# ESP32C6.net
KiCad netlist of a schematic drawn in Altium Designer
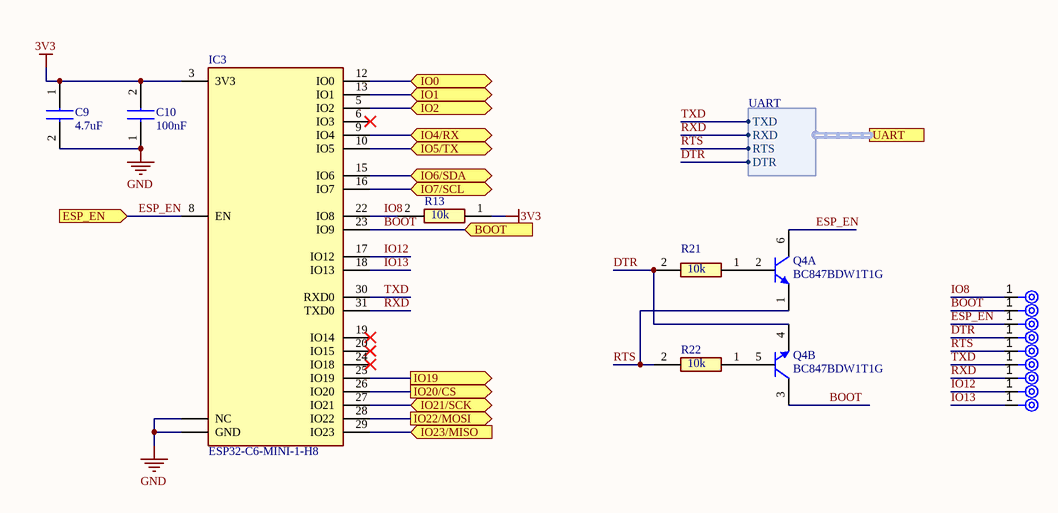
[diagram p0: ESP32C6.SchDoc]

(export (version "E")
  (design (tool "Eeschema 10.0.6"))
  (components
    (comp (ref "C9")
      (value "4.7uF")
      (footprint "SamacSys:CAPC1608X90N")
      (description "Capacitor")
      (fields
        (field (name "MANUFACTURER_PART_NUMBER") "GRM188R61E475KE11J")
        (field (name "MOUSER PART NUMBER") "81-GRM188R61E475KE1J")
      )
      (libsource (lib "*") (part "GRM188R61E475KE11J"))
    )
    (comp (ref "C10")
      (value "100nF")
      (footprint "SamacSys:CAPC1005X70N")
      (description "Capacitor")
      (fields
        (field (name "MANUFACTURER_PART_NUMBER") "GRM155R61A104KA01D")
        (field (name "MOUSER PART NUMBER") "81-GRM155R61A104KA01")
      )
      (libsource (lib "*") (part "GRM155R61A104KA01D"))
    )
    (comp (ref "IC3")
      (value "ESP32-C6-MINI-1-H8")
      (footprint "SamacSys:ESP32C6MINI1H8")
      (description "Integrated Circuit")
      (fields (field (name "MOUSER PART NUMBER") "356-ESP32C6MINI1H8"))
      (libsource (lib "SamacSys") (part "ESP32-C6-MINI-1-H8"))
    )
    (comp (ref "Q4")
      (value "BC847BDW1T1G")
      (footprint "ONSC-SOT-363-6-419B-02_W_V")
      (description "Dual General Purpose Transistors, NPN, 6-Pin SOT-363, Pb-Free, Tape and Reel")
      (fields (field (name "MANUFACTURER") "On Semiconductor"))
      (libsource (lib "Altium Content Vault") (part "ONSC-NPN_NPN-6_F"))
    )
    (comp (ref "R13")
      (value "10k")
      (footprint "SamacSys:RESC1005X35N")
      (description "Resistor")
      (fields
        (field (name "MANUFACTURER_PART_NUMBER") "RT0402FRE0710KL")
        (field (name "MOUSER PART NUMBER") "603-RT0402FRE0710KL")
      )
      (libsource (lib "SamacSys") (part "RT0402FRE0710KL"))
    )
    (comp (ref "R21")
      (value "10k")
      (footprint "SamacSys:RESC1005X35N")
      (description "Resistor")
      (fields
        (field (name "MANUFACTURER_PART_NUMBER") "RT0402FRE0710KL")
        (field (name "MOUSER PART NUMBER") "603-RT0402FRE0710KL")
      )
      (libsource (lib "SamacSys") (part "RT0402FRE0710KL"))
    )
    (comp (ref "R22")
      (value "10k")
      (footprint "SamacSys:RESC1005X35N")
      (description "Resistor")
      (fields
        (field (name "MANUFACTURER_PART_NUMBER") "RT0402FRE0710KL")
        (field (name "MOUSER PART NUMBER") "603-RT0402FRE0710KL")
      )
      (libsource (lib "SamacSys") (part "RT0402FRE0710KL"))
    )
    (comp (ref "TP4")
      (value "TPAD6R")
      (footprint "TP06R")
      (description "0.6mm round")
      (libsource (lib "Západočeská Univerzita V Plzni") (part "CMP-001-0001-4"))
    )
    (comp (ref "TP5")
      (value "TPAD6R")
      (footprint "TP06R")
      (description "0.6mm round")
      (libsource (lib "Západočeská Univerzita V Plzni") (part "CMP-001-0001-4"))
    )
    (comp (ref "TP6")
      (value "TPAD6R")
      (footprint "TP06R")
      (description "0.6mm round")
      (libsource (lib "Západočeská Univerzita V Plzni") (part "CMP-001-0001-4"))
    )
    (comp (ref "TP7")
      (value "TPAD6R")
      (footprint "TP06R")
      (description "0.6mm round")
      (libsource (lib "Západočeská Univerzita V Plzni") (part "CMP-001-0001-4"))
    )
    (comp (ref "TP8")
      (value "TPAD6R")
      (footprint "TP06R")
      (description "0.6mm round")
      (libsource (lib "Západočeská Univerzita V Plzni") (part "CMP-001-0001-4"))
    )
    (comp (ref "TP9")
      (value "TPAD6R")
      (footprint "TP06R")
      (description "0.6mm round")
      (libsource (lib "Západočeská Univerzita V Plzni") (part "CMP-001-0001-4"))
    )
    (comp (ref "TP10")
      (value "TPAD6R")
      (footprint "TP06R")
      (description "0.6mm round")
      (libsource (lib "Západočeská Univerzita V Plzni") (part "CMP-001-0001-4"))
    )
    (comp (ref "TP11")
      (value "TPAD6R")
      (footprint "TP06R")
      (description "0.6mm round")
      (libsource (lib "Západočeská Univerzita V Plzni") (part "CMP-001-0001-4"))
    )
    (comp (ref "TP12")
      (value "TPAD6R")
      (footprint "TP06R")
      (description "0.6mm round")
      (libsource (lib "Západočeská Univerzita V Plzni") (part "CMP-001-0001-4"))
    )
  )
  (nets
    (net (code "2") (name "/BOOT") (class "Default")
      (node (ref "IC3") (pin "23") (pinfunction "IO9_23") (pintype "passive"))
      (node (ref "Q4") (pin "3") (pinfunction "C_3") (pintype "passive"))
      (node (ref "TP5") (pin "1") (pinfunction "TP_1") (pintype "passive"))
    )
    (net (code "3") (name "/DTR") (class "Default")
      (node (ref "Q4") (pin "4") (pinfunction "E_4") (pintype "passive"))
      (node (ref "R21") (pin "2") (pinfunction "2_2") (pintype "passive"))
      (node (ref "TP7") (pin "1") (pinfunction "TP_1") (pintype "passive"))
    )
    (net (code "4") (name "/ESP_EN") (class "Default")
      (node (ref "IC3") (pin "8") (pinfunction "EN_8") (pintype "passive"))
      (node (ref "Q4") (pin "6") (pinfunction "C_6") (pintype "passive"))
      (node (ref "TP6") (pin "1") (pinfunction "TP_1") (pintype "passive"))
    )
    (net (code "5") (name "/IO0") (class "Default")
      (node (ref "IC3") (pin "12") (pinfunction "IO0_12") (pintype "passive"))
    )
    (net (code "6") (name "/IO1") (class "Default")
      (node (ref "IC3") (pin "13") (pinfunction "IO1_13") (pintype "passive"))
    )
    (net (code "7") (name "/IO2") (class "Default")
      (node (ref "IC3") (pin "5") (pinfunction "IO2_5") (pintype "passive"))
    )
    (net (code "8") (name "/IO4{slash}RX") (class "Default")
      (node (ref "IC3") (pin "9") (pinfunction "IO4_9") (pintype "passive"))
    )
    (net (code "9") (name "/IO5{slash}TX") (class "Default")
      (node (ref "IC3") (pin "10") (pinfunction "IO5_10") (pintype "passive"))
    )
    (net (code "10") (name "/IO6{slash}SDA") (class "Default")
      (node (ref "IC3") (pin "15") (pinfunction "IO6_15") (pintype "passive"))
    )
    (net (code "11") (name "/IO7{slash}SCL") (class "Default")
      (node (ref "IC3") (pin "16") (pinfunction "IO7_16") (pintype "passive"))
    )
    (net (code "12") (name "/IO8") (class "Default")
      (node (ref "IC3") (pin "22") (pinfunction "IO8_22") (pintype "passive"))
      (node (ref "R13") (pin "2") (pinfunction "2_2") (pintype "passive"))
      (node (ref "TP4") (pin "1") (pinfunction "TP_1") (pintype "passive"))
    )
    (net (code "13") (name "/IO12") (class "Default")
      (node (ref "IC3") (pin "17") (pinfunction "IO12_17") (pintype "passive"))
      (node (ref "TP11") (pin "1") (pinfunction "TP_1") (pintype "passive"))
    )
    (net (code "14") (name "/IO13") (class "Default")
      (node (ref "IC3") (pin "18") (pinfunction "IO13_18") (pintype "passive"))
      (node (ref "TP12") (pin "1") (pinfunction "TP_1") (pintype "passive"))
    )
    (net (code "15") (name "/IO19") (class "Default")
      (node (ref "IC3") (pin "25") (pinfunction "IO19_25") (pintype "passive"))
    )
    (net (code "16") (name "/IO20{slash}CS") (class "Default")
      (node (ref "IC3") (pin "26") (pinfunction "IO20_26") (pintype "passive"))
    )
    (net (code "17") (name "/IO21{slash}SCK") (class "Default")
      (node (ref "IC3") (pin "27") (pinfunction "IO21_27") (pintype "passive"))
    )
    (net (code "18") (name "/IO22{slash}MOSI") (class "Default")
      (node (ref "IC3") (pin "28") (pinfunction "IO22_28") (pintype "passive"))
    )
    (net (code "19") (name "/IO23{slash}MISO") (class "Default")
      (node (ref "IC3") (pin "29") (pinfunction "IO23_29") (pintype "passive"))
    )
    (net (code "20") (name "/RTS") (class "Default")
      (node (ref "Q4") (pin "1") (pinfunction "E_1") (pintype "passive"))
      (node (ref "R22") (pin "2") (pinfunction "2_2") (pintype "passive"))
      (node (ref "TP8") (pin "1") (pinfunction "TP_1") (pintype "passive"))
    )
    (net (code "21") (name "/RXD") (class "Default")
      (node (ref "IC3") (pin "31") (pinfunction "TXD0_31") (pintype "passive"))
      (node (ref "TP10") (pin "1") (pinfunction "TP_1") (pintype "passive"))
    )
    (net (code "22") (name "/TXD") (class "Default")
      (node (ref "IC3") (pin "30") (pinfunction "RXD0_30") (pintype "passive"))
      (node (ref "TP9") (pin "1") (pinfunction "TP_1") (pintype "passive"))
    )
    (net (code "24") (name "3V3") (class "Default")
      (node (ref "C10") (pin "2") (pinfunction "2_2") (pintype "passive"))
      (node (ref "C9") (pin "1") (pinfunction "1_1") (pintype "passive"))
      (node (ref "IC3") (pin "3") (pinfunction "3V3_3") (pintype "passive"))
      (node (ref "R13") (pin "1") (pinfunction "1_1") (pintype "passive"))
    )
    (net (code "25") (name "GND") (class "Default")
      (node (ref "C10") (pin "1") (pinfunction "1_1") (pintype "passive"))
      (node (ref "C9") (pin "2") (pinfunction "2_2") (pintype "passive"))
      (node (ref "IC3") (pin "1") (pinfunction "GND_1") (pintype "passive"))
      (node (ref "IC3") (pin "21") (pinfunction "NC_21") (pintype "passive"))
    )
    (net (code "26") (name "Net-(Q4A-B)") (class "Default")
      (node (ref "Q4") (pin "2") (pinfunction "B_2") (pintype "passive"))
      (node (ref "R21") (pin "1") (pinfunction "1_1") (pintype "passive"))
    )
    (net (code "27") (name "Net-(Q4B-B)") (class "Default")
      (node (ref "Q4") (pin "5") (pinfunction "B_5") (pintype "passive"))
      (node (ref "R22") (pin "1") (pinfunction "1_1") (pintype "passive"))
    )
    (net (code "28") (name "unconnected-(IC3-IO3-Pad6)") (class "Default")
      (node (ref "IC3") (pin "6") (pinfunction "IO3_6") (pintype "passive+no_connect"))
    )
    (net (code "29") (name "unconnected-(IC3-IO14-Pad19)") (class "Default")
      (node (ref "IC3") (pin "19") (pinfunction "IO14_19") (pintype "passive+no_connect"))
    )
    (net (code "30") (name "unconnected-(IC3-IO15-Pad20)") (class "Default")
      (node (ref "IC3") (pin "20") (pinfunction "IO15_20") (pintype "passive+no_connect"))
    )
    (net (code "31") (name "unconnected-(IC3-IO18-Pad24)") (class "Default")
      (node (ref "IC3") (pin "24") (pinfunction "IO18_24") (pintype "passive+no_connect"))
    )
  )
)
